# Modem-GPRS.net
KiCad netlist of a schematic drawn in Altium Designer
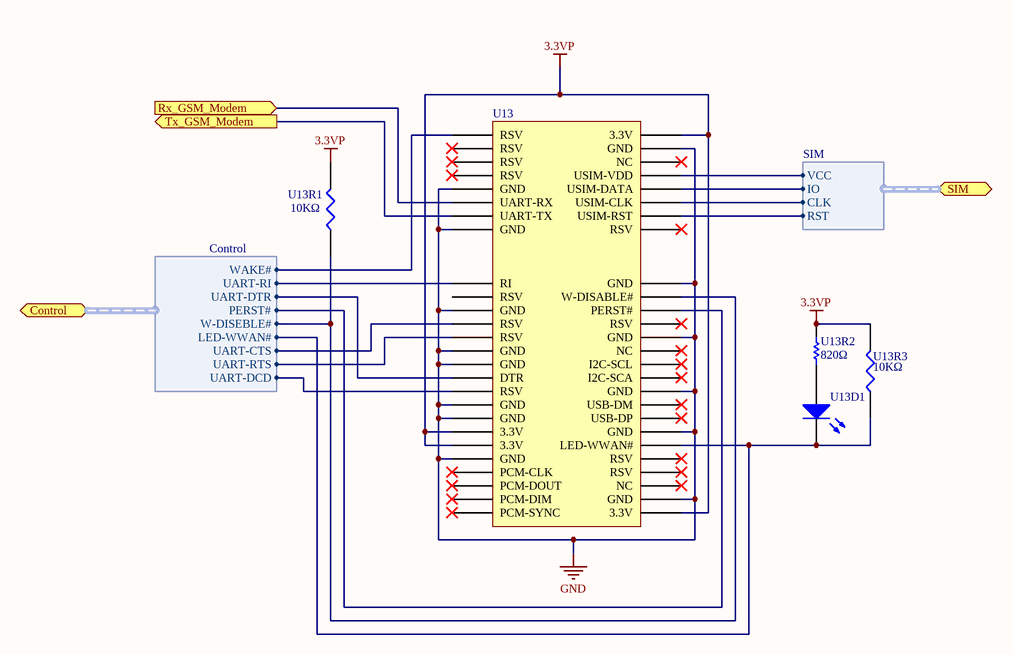
[diagram p0: Modem-GPRS.SchDoc]

(export (version "E")
  (design (tool "Eeschema 10.0.6"))
  (components
    (comp (ref "U13")
      (value "MiniPCIe")
      (footprint "MiniPCI-52")
      (description "Mini PCIe")
      (fields
        (field (name "MANUFACTURER") "TE Connectivity AMP Connectors")
        (field (name "MANUFACTURER PART NUMBER") "2041119-1")
      )
      (libsource (lib "LibreriaEstandar2") (part "PCIM"))
    )
    (comp (ref "U13D1")
      (value "LED2")
      (footprint "0805-LEDG")
      (description "WL-SMCW SMD mono-color chip LED waterclear 0805 Green")
      (fields
        (field (name "MANUFACTURER") "WURTH ELEKTRONIK")
        (field (name "MANUFACTURER PART NUMBER") "150080GS75000")
      )
      (libsource (lib "Miscellaneous Devices") (part "LED2"))
    )
    (comp (ref "U13R1")
      (value "10KΩ")
      (footprint "0805-RES")
      (description "10 kOhms ±5% 0.125W, 1/8W Chip Resistor 0805")
      (fields
        (field (name "MANUFACTURER PART NUMBER") "RC0805JR-0710KL")
        (field (name "MANUFACTURER") "Yageo")
      )
      (libsource (lib "*") (part "RES1"))
    )
    (comp (ref "U13R2")
      (value "820Ω")
      (footprint "0805-RES")
      (fields
        (field (name "MANUFACTURER") "PANASONIC ELECTRONIC COMPONENTS")
        (field (name "MANUFACTURER PART NUMBER") "ERJ-6GEYJ821V")
      )
      (libsource (lib "Miscellaneous Devices") (part "Res1"))
    )
    (comp (ref "U13R3")
      (value "10KΩ")
      (footprint "0805-RES")
      (description "10 kOhms ±5% 0.125W, 1/8W Chip Resistor 0805")
      (fields
        (field (name "MANUFACTURER PART NUMBER") "RC0805JR-0710KL")
        (field (name "MANUFACTURER") "Yageo")
      )
      (libsource (lib "*") (part "RES1"))
    )
  )
  (nets
    (net (code "3") (name "/CLK") (class "Default")
      (node (ref "U13") (pin "12") (pinfunction "USIM-CLK_12") (pintype "passive"))
    )
    (net (code "4") (name "/IO") (class "Default")
      (node (ref "U13") (pin "10") (pinfunction "USIM-DATA_10") (pintype "passive"))
    )
    (net (code "5") (name "/LED-WWAN#") (class "Default")
      (node (ref "U13") (pin "42") (pinfunction "LED-WWAN#_42") (pintype "passive"))
      (node (ref "U13D1") (pin "2") (pinfunction "K_2") (pintype "passive"))
      (node (ref "U13R3") (pin "1") (pinfunction "1_1") (pintype "passive"))
    )
    (net (code "6") (name "/PERST#") (class "Default")
      (node (ref "U13") (pin "22") (pinfunction "PERST#_22") (pintype "passive"))
    )
    (net (code "7") (name "/RST") (class "Default")
      (node (ref "U13") (pin "14") (pinfunction "USIM-RST_14") (pintype "passive"))
    )
    (net (code "8") (name "/Rx_GSM_Modem") (class "Default")
      (node (ref "U13") (pin "11") (pinfunction "UART-RX_11") (pintype "passive"))
    )
    (net (code "9") (name "/Tx_GSM_Modem") (class "Default")
      (node (ref "U13") (pin "13") (pinfunction "UART-TX_13") (pintype "passive"))
    )
    (net (code "10") (name "/UART-CTS") (class "Default")
      (node (ref "U13") (pin "23") (pinfunction "RSV_23") (pintype "passive"))
    )
    (net (code "11") (name "/UART-DCD") (class "Default")
      (node (ref "U13") (pin "33") (pinfunction "RSV_33") (pintype "passive"))
    )
    (net (code "12") (name "/UART-DTR") (class "Default")
      (node (ref "U13") (pin "31") (pinfunction "DTR_31") (pintype "passive"))
    )
    (net (code "13") (name "/UART-RI") (class "Default")
      (node (ref "U13") (pin "17") (pinfunction "RI_17") (pintype "passive"))
    )
    (net (code "14") (name "/UART-RTS") (class "Default")
      (node (ref "U13") (pin "25") (pinfunction "RSV_25") (pintype "passive"))
    )
    (net (code "15") (name "/VCC") (class "Default")
      (node (ref "U13") (pin "8") (pinfunction "USIM-VDD_8") (pintype "passive"))
    )
    (net (code "16") (name "/W-DISEBLE#") (class "Default")
      (node (ref "U13") (pin "20") (pinfunction "W-DISABLE#_20") (pintype "passive"))
      (node (ref "U13R1") (pin "1") (pinfunction "1_1") (pintype "passive"))
    )
    (net (code "17") (name "/WAKE#") (class "Default")
      (node (ref "U13") (pin "1") (pinfunction "RSV_1") (pintype "passive"))
    )
    (net (code "20") (name "3.3VP") (class "Default")
      (node (ref "U13") (pin "2") (pinfunction "3.3V_2") (pintype "passive"))
      (node (ref "U13") (pin "39") (pinfunction "3.3V_39") (pintype "passive"))
      (node (ref "U13") (pin "41") (pinfunction "3.3V_41") (pintype "passive"))
      (node (ref "U13") (pin "52") (pinfunction "3.3V_52") (pintype "passive"))
      (node (ref "U13R1") (pin "2") (pinfunction "2_2") (pintype "passive"))
      (node (ref "U13R2") (pin "2") (pinfunction "2_2") (pintype "passive"))
      (node (ref "U13R3") (pin "2") (pinfunction "2_2") (pintype "passive"))
    )
    (net (code "21") (name "GND") (class "Default")
      (node (ref "U13") (pin "15") (pinfunction "GND_15") (pintype "passive"))
      (node (ref "U13") (pin "18") (pinfunction "GND_18") (pintype "passive"))
      (node (ref "U13") (pin "21") (pinfunction "GND_21") (pintype "passive"))
      (node (ref "U13") (pin "26") (pinfunction "GND_26") (pintype "passive"))
      (node (ref "U13") (pin "27") (pinfunction "GND_27") (pintype "passive"))
      (node (ref "U13") (pin "29") (pinfunction "GND_29") (pintype "passive"))
      (node (ref "U13") (pin "34") (pinfunction "GND_34") (pintype "passive"))
      (node (ref "U13") (pin "35") (pinfunction "GND_35") (pintype "passive"))
      (node (ref "U13") (pin "37") (pinfunction "GND_37") (pintype "passive"))
      (node (ref "U13") (pin "4") (pinfunction "GND_4") (pintype "passive"))
      (node (ref "U13") (pin "40") (pinfunction "GND_40") (pintype "passive"))
      (node (ref "U13") (pin "43") (pinfunction "GND_43") (pintype "passive"))
      (node (ref "U13") (pin "50") (pinfunction "GND_50") (pintype "passive"))
      (node (ref "U13") (pin "9") (pinfunction "GND_9") (pintype "passive"))
    )
    (net (code "22") (name "Net-(U13D1-A)") (class "Default")
      (node (ref "U13D1") (pin "1") (pinfunction "A_1") (pintype "passive"))
      (node (ref "U13R2") (pin "1") (pinfunction "1_1") (pintype "passive"))
    )
    (net (code "23") (name "unconnected-(U13-I2C-SCA-Pad32)") (class "Default")
      (node (ref "U13") (pin "32") (pinfunction "I2C-SCA_32") (pintype "passive+no_connect"))
    )
    (net (code "24") (name "unconnected-(U13-I2C-SCL-Pad30)") (class "Default")
      (node (ref "U13") (pin "30") (pinfunction "I2C-SCL_30") (pintype "passive+no_connect"))
    )
    (net (code "25") (name "unconnected-(U13-NC-Pad6)") (class "Default")
      (node (ref "U13") (pin "6") (pinfunction "NC_6") (pintype "passive+no_connect"))
    )
    (net (code "26") (name "unconnected-(U13-NC-Pad28)") (class "Default")
      (node (ref "U13") (pin "28") (pinfunction "NC_28") (pintype "passive+no_connect"))
    )
    (net (code "27") (name "unconnected-(U13-NC-Pad48)") (class "Default")
      (node (ref "U13") (pin "48") (pinfunction "NC_48") (pintype "passive+no_connect"))
    )
    (net (code "28") (name "unconnected-(U13-PCM-CLK-Pad45)") (class "Default")
      (node (ref "U13") (pin "45") (pinfunction "PCM-CLK_45") (pintype "passive+no_connect"))
    )
    (net (code "29") (name "unconnected-(U13-PCM-DIM-Pad49)") (class "Default")
      (node (ref "U13") (pin "49") (pinfunction "PCM-DIM_49") (pintype "passive+no_connect"))
    )
    (net (code "30") (name "unconnected-(U13-PCM-DOUT-Pad47)") (class "Default")
      (node (ref "U13") (pin "47") (pinfunction "PCM-DOUT_47") (pintype "passive+no_connect"))
    )
    (net (code "31") (name "unconnected-(U13-PCM-SYNC-Pad51)") (class "Default")
      (node (ref "U13") (pin "51") (pinfunction "PCM-SYNC_51") (pintype "passive+no_connect"))
    )
    (net (code "32") (name "unconnected-(U13-RSV-Pad3)") (class "Default")
      (node (ref "U13") (pin "3") (pinfunction "RSV_3") (pintype "passive+no_connect"))
    )
    (net (code "33") (name "unconnected-(U13-RSV-Pad5)") (class "Default")
      (node (ref "U13") (pin "5") (pinfunction "RSV_5") (pintype "passive+no_connect"))
    )
    (net (code "34") (name "unconnected-(U13-RSV-Pad7)") (class "Default")
      (node (ref "U13") (pin "7") (pinfunction "RSV_7") (pintype "passive+no_connect"))
    )
    (net (code "35") (name "unconnected-(U13-RSV-Pad16)") (class "Default")
      (node (ref "U13") (pin "16") (pinfunction "RSV_16") (pintype "passive+no_connect"))
    )
    (net (code "36") (name "unconnected-(U13-RSV-Pad19)") (class "Default")
      (node (ref "U13") (pin "19") (pinfunction "RSV_19") (pintype "passive"))
    )
    (net (code "37") (name "unconnected-(U13-RSV-Pad24)") (class "Default")
      (node (ref "U13") (pin "24") (pinfunction "RSV_24") (pintype "passive+no_connect"))
    )
    (net (code "38") (name "unconnected-(U13-RSV-Pad44)") (class "Default")
      (node (ref "U13") (pin "44") (pinfunction "RSV_44") (pintype "passive+no_connect"))
    )
    (net (code "39") (name "unconnected-(U13-RSV-Pad46)") (class "Default")
      (node (ref "U13") (pin "46") (pinfunction "RSV_46") (pintype "passive+no_connect"))
    )
    (net (code "40") (name "unconnected-(U13-USB-DM-Pad36)") (class "Default")
      (node (ref "U13") (pin "36") (pinfunction "USB-DM_36") (pintype "passive+no_connect"))
    )
    (net (code "41") (name "unconnected-(U13-USB-DP-Pad38)") (class "Default")
      (node (ref "U13") (pin "38") (pinfunction "USB-DP_38") (pintype "passive+no_connect"))
    )
  )
)
